# CPU.net
KiCad netlist of a schematic drawn in Altium Designer
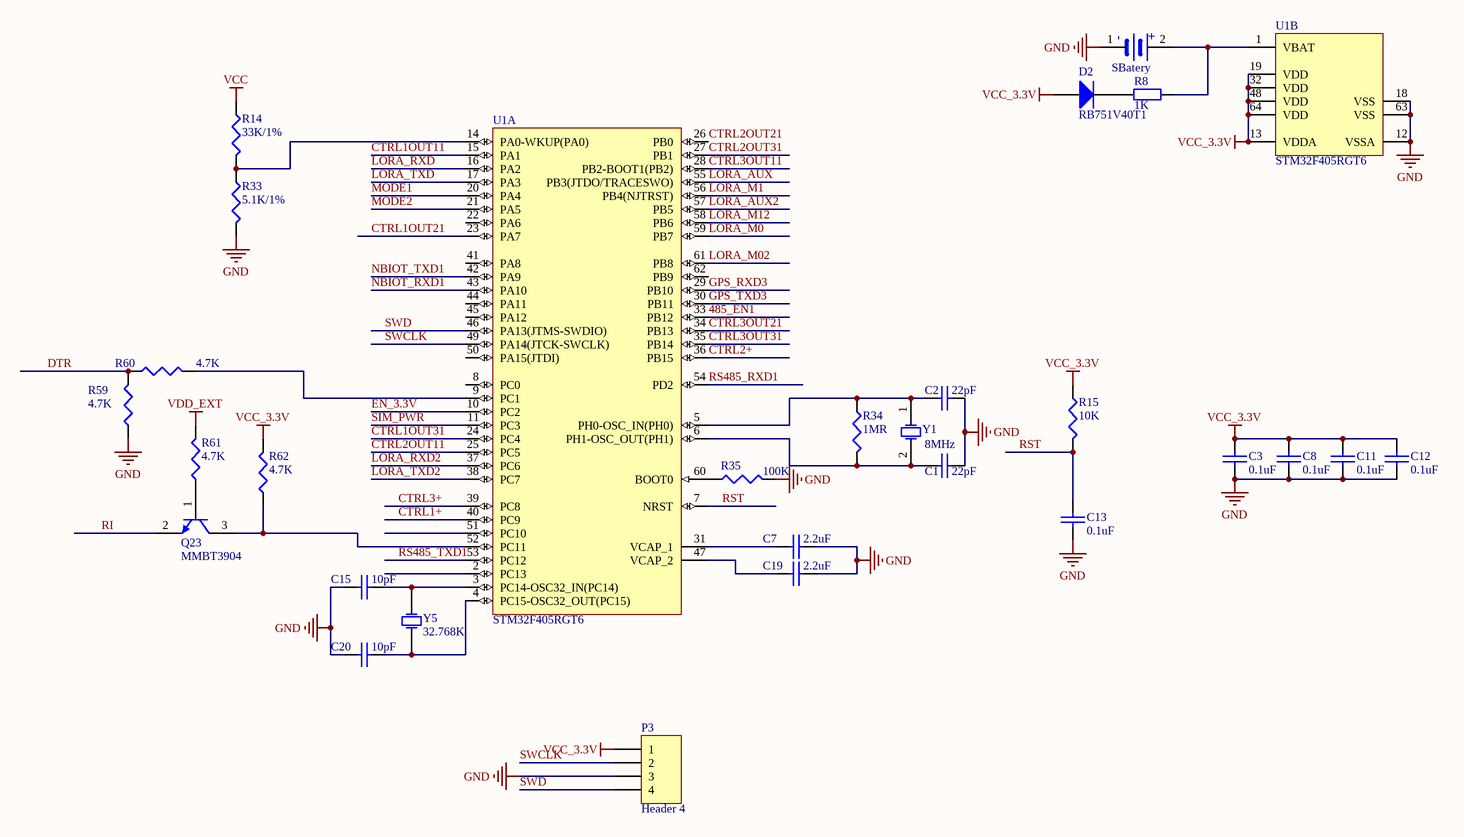
[diagram p0: CPU.SchDoc]

(export (version "E")
  (design (tool "Eeschema 10.0.6"))
  (components
    (comp (ref "C1")
      (value "22pF")
      (footprint "0603c")
      (description "Capacitor")
      (libsource (lib "SM") (part "CAP"))
    )
    (comp (ref "C2")
      (value "22pF")
      (footprint "0603c")
      (description "Capacitor")
      (libsource (lib "SM") (part "CAP"))
    )
    (comp (ref "C3")
      (value "0.1uF")
      (footprint "0603c")
      (description "Capacitor")
      (libsource (lib "SM") (part "CAP"))
    )
    (comp (ref "C7")
      (value "2.2uF")
      (footprint "0603c")
      (description "Capacitor")
      (libsource (lib "SM") (part "CAP"))
    )
    (comp (ref "C8")
      (value "0.1uF")
      (footprint "0603c")
      (description "Capacitor")
      (libsource (lib "SM") (part "CAP"))
    )
    (comp (ref "C11")
      (value "0.1uF")
      (footprint "0603c")
      (description "Capacitor")
      (libsource (lib "SM") (part "CAP"))
    )
    (comp (ref "C12")
      (value "0.1uF")
      (footprint "0603c")
      (description "Capacitor")
      (libsource (lib "SM") (part "CAP"))
    )
    (comp (ref "C13")
      (value "0.1uF")
      (footprint "0603c")
      (description "Capacitor")
      (libsource (lib "SM") (part "CAP"))
    )
    (comp (ref "C15")
      (value "10pF")
      (footprint "0603c")
      (description "Capacitor")
      (libsource (lib "SM") (part "CAP"))
    )
    (comp (ref "C19")
      (value "2.2uF")
      (footprint "0603c")
      (description "Capacitor")
      (libsource (lib "SM") (part "CAP"))
    )
    (comp (ref "C20")
      (value "10pF")
      (footprint "0603c")
      (description "Capacitor")
      (libsource (lib "SM") (part "CAP"))
    )
    (comp (ref "D2")
      (value "RB751V40T1")
      (footprint "SOD323")
      (description "Default Diode")
      (fields (field (name "PUBLISHER") "Altium Limited"))
      (libsource (lib "Miscellaneous Devices") (part "Diode"))
    )
    (comp (ref "P3")
      (value "Header 4")
      (footprint "HDR1X4")
      (description "Header, 4-Pin")
      (fields (field (name "PUBLISHER") "Altium Limited"))
      (libsource (lib "Miscellaneous Connectors") (part "Header 4"))
    )
    (comp (ref "Q23") (value "MMBT3904") (footprint "SOT23-3") (libsource (lib "Schlib1") (part "NPN")))
    (comp (ref "R8")
      (value "1K")
      (footprint "0603R")
      (description "Resistor")
      (fields (field (name "PUBLISHER") "Altium Limited"))
      (libsource (lib "Miscellaneous Devices") (part "Res2"))
    )
    (comp (ref "R14")
      (value "33K/1%")
      (footprint "0603R")
      (description "Resistor")
      (fields (field (name "PUBLISHER") "Altium Limited"))
      (libsource (lib "SM") (part "Res3"))
    )
    (comp (ref "R15")
      (value "10K")
      (footprint "0603R")
      (description "Resistor")
      (fields (field (name "PUBLISHER") "Altium Limited"))
      (libsource (lib "SM") (part "Res3"))
    )
    (comp (ref "R33")
      (value "5.1K/1%")
      (footprint "0603R")
      (description "Resistor")
      (fields (field (name "PUBLISHER") "Altium Limited"))
      (libsource (lib "SM") (part "Res3"))
    )
    (comp (ref "R34")
      (value "1MR")
      (footprint "0603R")
      (description "Resistor")
      (fields (field (name "PUBLISHER") "Altium Limited"))
      (libsource (lib "SM") (part "Res3"))
    )
    (comp (ref "R35")
      (value "100K")
      (footprint "0603R")
      (description "Resistor")
      (fields (field (name "PUBLISHER") "Altium Limited"))
      (libsource (lib "SM") (part "Res3"))
    )
    (comp (ref "R59")
      (value "4.7K")
      (footprint "0603R")
      (libsource (lib "ZWLIntegrated_Library") (part "RES1"))
    )
    (comp (ref "R60")
      (value "4.7K")
      (footprint "0603R")
      (libsource (lib "ZWLIntegrated_Library") (part "RES1"))
    )
    (comp (ref "R61")
      (value "4.7K")
      (footprint "0603R")
      (libsource (lib "ZWLIntegrated_Library") (part "RES1"))
    )
    (comp (ref "R62")
      (value "4.7K")
      (footprint "0603R")
      (libsource (lib "ZWLIntegrated_Library") (part "RES1"))
    )
    (comp (ref "SBatery")
      (value "SBatery")
      (footprint "MS621FE")
      (libsource (lib "Myself_1") (part "SBatery"))
    )
    (comp (ref "U1")
      (value "STM32F405RGT6")
      (footprint "LQFP-64")
      (fields (field (name "MANUFACTURER") "STMicroelectronics"))
      (libsource (lib "STMicroelectronics STM32 F4") (part "STM32F405RGT6"))
    )
    (comp (ref "Y1")
      (value "8MHz")
      (footprint "CRAY_5032")
      (description "Crystal Oscillator")
      (fields (field (name "PUBLISHER") "Altium Limited"))
      (libsource (lib "") (part "XTAL_1"))
    )
    (comp (ref "Y5")
      (value "32.768K")
      (footprint "32.768K")
      (description "Crystal Oscillator")
      (fields (field (name "PUBLISHER") "Altium Limited"))
      (libsource (lib "Miscellaneous Devices") (part "XTAL"))
    )
  )
  (nets
    (net (code "1") (name "/485_EN1") (class "Default")
      (node (ref "U1") (pin "33") (pinfunction "PB12_33") (pintype "bidirectional"))
    )
    (net (code "2") (name "/CTRL1+") (class "Default")
      (node (ref "U1") (pin "40") (pinfunction "PC9_40") (pintype "bidirectional"))
    )
    (net (code "3") (name "/CTRL1OUT11") (class "Default")
      (node (ref "U1") (pin "15") (pinfunction "PA1_15") (pintype "bidirectional"))
    )
    (net (code "4") (name "/CTRL1OUT21") (class "Default")
      (node (ref "U1") (pin "23") (pinfunction "PA7_23") (pintype "bidirectional"))
    )
    (net (code "5") (name "/CTRL1OUT31") (class "Default")
      (node (ref "U1") (pin "24") (pinfunction "PC4_24") (pintype "bidirectional"))
    )
    (net (code "6") (name "/CTRL2+") (class "Default")
      (node (ref "U1") (pin "36") (pinfunction "PB15_36") (pintype "bidirectional"))
    )
    (net (code "7") (name "/CTRL2OUT11") (class "Default")
      (node (ref "U1") (pin "25") (pinfunction "PC5_25") (pintype "bidirectional"))
    )
    (net (code "8") (name "/CTRL2OUT21") (class "Default")
      (node (ref "U1") (pin "26") (pinfunction "PB0_26") (pintype "bidirectional"))
    )
    (net (code "9") (name "/CTRL2OUT31") (class "Default")
      (node (ref "U1") (pin "27") (pinfunction "PB1_27") (pintype "bidirectional"))
    )
    (net (code "10") (name "/CTRL3+") (class "Default")
      (node (ref "U1") (pin "39") (pinfunction "PC8_39") (pintype "bidirectional"))
    )
    (net (code "11") (name "/CTRL3OUT11") (class "Default")
      (node (ref "U1") (pin "28") (pinfunction "PB2-BOOT1(PB2)_28") (pintype "bidirectional"))
    )
    (net (code "12") (name "/CTRL3OUT21") (class "Default")
      (node (ref "U1") (pin "34") (pinfunction "PB13_34") (pintype "bidirectional"))
    )
    (net (code "13") (name "/CTRL3OUT31") (class "Default")
      (node (ref "U1") (pin "35") (pinfunction "PB14_35") (pintype "bidirectional"))
    )
    (net (code "14") (name "/DTR") (class "Default")
      (node (ref "R59") (pin "2") (pinfunction "2_2") (pintype "passive"))
      (node (ref "R60") (pin "1") (pinfunction "1_1") (pintype "passive"))
    )
    (net (code "15") (name "/EN_3.3V") (class "Default")
      (node (ref "U1") (pin "10") (pinfunction "PC2_10") (pintype "bidirectional"))
    )
    (net (code "16") (name "/GPS_RXD3") (class "Default")
      (node (ref "U1") (pin "29") (pinfunction "PB10_29") (pintype "bidirectional"))
    )
    (net (code "17") (name "/GPS_TXD3") (class "Default")
      (node (ref "U1") (pin "30") (pinfunction "PB11_30") (pintype "bidirectional"))
    )
    (net (code "18") (name "/LORA_AUX") (class "Default")
      (node (ref "U1") (pin "55") (pinfunction "PB3(JTDO/TRACESWO)_55") (pintype "bidirectional"))
    )
    (net (code "19") (name "/LORA_AUX2") (class "Default")
      (node (ref "U1") (pin "57") (pinfunction "PB5_57") (pintype "bidirectional"))
    )
    (net (code "20") (name "/LORA_M0") (class "Default")
      (node (ref "U1") (pin "59") (pinfunction "PB7_59") (pintype "bidirectional"))
    )
    (net (code "21") (name "/LORA_M1") (class "Default")
      (node (ref "U1") (pin "56") (pinfunction "PB4(NJTRST)_56") (pintype "bidirectional"))
    )
    (net (code "22") (name "/LORA_M02") (class "Default")
      (node (ref "U1") (pin "61") (pinfunction "PB8_61") (pintype "bidirectional"))
    )
    (net (code "23") (name "/LORA_M12") (class "Default")
      (node (ref "U1") (pin "58") (pinfunction "PB6_58") (pintype "bidirectional"))
    )
    (net (code "24") (name "/LORA_RXD") (class "Default")
      (node (ref "U1") (pin "16") (pinfunction "PA2_16") (pintype "bidirectional"))
    )
    (net (code "25") (name "/LORA_RXD2") (class "Default")
      (node (ref "U1") (pin "37") (pinfunction "PC6_37") (pintype "bidirectional"))
    )
    (net (code "26") (name "/LORA_TXD") (class "Default")
      (node (ref "U1") (pin "17") (pinfunction "PA3_17") (pintype "bidirectional"))
    )
    (net (code "27") (name "/LORA_TXD2") (class "Default")
      (node (ref "U1") (pin "38") (pinfunction "PC7_38") (pintype "bidirectional"))
    )
    (net (code "28") (name "/MODE1") (class "Default")
      (node (ref "U1") (pin "20") (pinfunction "PA4_20") (pintype "bidirectional"))
    )
    (net (code "29") (name "/MODE2") (class "Default")
      (node (ref "U1") (pin "21") (pinfunction "PA5_21") (pintype "bidirectional"))
    )
    (net (code "30") (name "/NBIOT_RXD1") (class "Default")
      (node (ref "U1") (pin "43") (pinfunction "PA10_43") (pintype "bidirectional"))
    )
    (net (code "31") (name "/NBIOT_TXD1") (class "Default")
      (node (ref "U1") (pin "42") (pinfunction "PA9_42") (pintype "bidirectional"))
    )
    (net (code "32") (name "/RI") (class "Default")
      (node (ref "Q23") (pin "2") (pinfunction "E_2") (pintype "passive"))
    )
    (net (code "33") (name "/RS485_RXD1") (class "Default")
      (node (ref "U1") (pin "54") (pinfunction "PD2_54") (pintype "bidirectional"))
    )
    (net (code "34") (name "/RS485_TXD1") (class "Default")
      (node (ref "U1") (pin "53") (pinfunction "PC12_53") (pintype "bidirectional"))
    )
    (net (code "35") (name "/RST") (class "Default")
      (node (ref "C13") (pin "2") (pinfunction "2_2") (pintype "passive"))
      (node (ref "R15") (pin "2") (pinfunction "2_2") (pintype "passive"))
      (node (ref "U1") (pin "7") (pinfunction "NRST_7") (pintype "bidirectional"))
    )
    (net (code "36") (name "/SIM_PWR") (class "Default")
      (node (ref "U1") (pin "11") (pinfunction "PC3_11") (pintype "bidirectional"))
    )
    (net (code "37") (name "/SWCLK") (class "Default")
      (node (ref "P3") (pin "2") (pinfunction "2_2") (pintype "passive"))
      (node (ref "U1") (pin "49") (pinfunction "PA14(JTCK-SWCLK)_49") (pintype "bidirectional"))
    )
    (net (code "38") (name "/SWD") (class "Default")
      (node (ref "P3") (pin "4") (pinfunction "4_4") (pintype "passive"))
      (node (ref "U1") (pin "46") (pinfunction "PA13(JTMS-SWDIO)_46") (pintype "bidirectional"))
    )
    (net (code "39") (name "GND") (class "Default")
      (node (ref "C1") (pin "1") (pinfunction "1_1") (pintype "passive"))
      (node (ref "C11") (pin "1") (pinfunction "1_1") (pintype "passive"))
      (node (ref "C12") (pin "1") (pinfunction "1_1") (pintype "passive"))
      (node (ref "C13") (pin "1") (pinfunction "1_1") (pintype "passive"))
      (node (ref "C15") (pin "1") (pinfunction "1_1") (pintype "passive"))
      (node (ref "C19") (pin "1") (pinfunction "1_1") (pintype "passive"))
      (node (ref "C2") (pin "1") (pinfunction "1_1") (pintype "passive"))
      (node (ref "C20") (pin "1") (pinfunction "1_1") (pintype "passive"))
      (node (ref "C3") (pin "1") (pinfunction "1_1") (pintype "passive"))
      (node (ref "C7") (pin "1") (pinfunction "1_1") (pintype "passive"))
      (node (ref "C8") (pin "1") (pinfunction "1_1") (pintype "passive"))
      (node (ref "P3") (pin "3") (pinfunction "3_3") (pintype "passive"))
      (node (ref "R33") (pin "2") (pinfunction "2_2") (pintype "passive"))
      (node (ref "R35") (pin "2") (pinfunction "2_2") (pintype "passive"))
      (node (ref "R59") (pin "1") (pinfunction "1_1") (pintype "passive"))
      (node (ref "SBatery") (pin "1") (pinfunction "1_1") (pintype "passive"))
      (node (ref "U1") (pin "12") (pinfunction "VSSA_12") (pintype "power_in"))
      (node (ref "U1") (pin "18") (pinfunction "VSS_18") (pintype "power_in"))
      (node (ref "U1") (pin "63") (pinfunction "VSS_63") (pintype "power_in"))
    )
    (net (code "40") (name "Net-(D2-K)") (class "Default")
      (node (ref "D2") (pin "2") (pinfunction "K_2") (pintype "passive"))
      (node (ref "R8") (pin "1") (pinfunction "1_1") (pintype "passive"))
    )
    (net (code "41") (name "Net-(Q23-B)") (class "Default")
      (node (ref "Q23") (pin "1") (pinfunction "B_1") (pintype "passive"))
      (node (ref "R61") (pin "1") (pinfunction "1_1") (pintype "passive"))
    )
    (net (code "42") (name "Net-(Q23-C)") (class "Default")
      (node (ref "Q23") (pin "3") (pinfunction "C_3") (pintype "passive"))
      (node (ref "R62") (pin "1") (pinfunction "1_1") (pintype "passive"))
      (node (ref "U1") (pin "52") (pinfunction "PC11_52") (pintype "bidirectional"))
    )
    (net (code "43") (name "Net-(U1A-BOOT0)") (class "Default")
      (node (ref "R35") (pin "1") (pinfunction "1_1") (pintype "passive"))
      (node (ref "U1") (pin "60") (pinfunction "BOOT0_60") (pintype "input"))
    )
    (net (code "44") (name "Net-(U1A-PA0-WKUP(PA0))") (class "Default")
      (node (ref "R14") (pin "2") (pinfunction "2_2") (pintype "passive"))
      (node (ref "R33") (pin "1") (pinfunction "1_1") (pintype "passive"))
      (node (ref "U1") (pin "14") (pinfunction "PA0-WKUP(PA0)_14") (pintype "bidirectional"))
    )
    (net (code "45") (name "Net-(U1A-PC1)") (class "Default")
      (node (ref "R60") (pin "2") (pinfunction "2_2") (pintype "passive"))
      (node (ref "U1") (pin "9") (pinfunction "PC1_9") (pintype "bidirectional"))
    )
    (net (code "46") (name "Net-(U1A-PC14-OSC32_IN(PC14))") (class "Default")
      (node (ref "C15") (pin "2") (pinfunction "2_2") (pintype "passive"))
      (node (ref "U1") (pin "3") (pinfunction "PC14-OSC32_IN(PC14)_3") (pintype "bidirectional"))
      (node (ref "Y5") (pin "1") (pinfunction "OSC1_1") (pintype "passive"))
    )
    (net (code "47") (name "Net-(U1A-PC15-OSC32_OUT(PC15))") (class "Default")
      (node (ref "C20") (pin "2") (pinfunction "2_2") (pintype "passive"))
      (node (ref "U1") (pin "4") (pinfunction "PC15-OSC32_OUT(PC15)_4") (pintype "bidirectional"))
      (node (ref "Y5") (pin "2") (pinfunction "OSC2_2") (pintype "passive"))
    )
    (net (code "48") (name "Net-(U1A-PH0-OSC_IN(PH0))") (class "Default")
      (node (ref "C2") (pin "2") (pinfunction "2_2") (pintype "passive"))
      (node (ref "R34") (pin "1") (pinfunction "1_1") (pintype "passive"))
      (node (ref "U1") (pin "5") (pinfunction "PH0-OSC_IN(PH0)_5") (pintype "bidirectional"))
      (node (ref "Y1") (pin "1") (pinfunction "OSC1_1") (pintype "passive"))
    )
    (net (code "49") (name "Net-(U1A-PH1-OSC_OUT(PH1))") (class "Default")
      (node (ref "C1") (pin "2") (pinfunction "2_2") (pintype "passive"))
      (node (ref "R34") (pin "2") (pinfunction "2_2") (pintype "passive"))
      (node (ref "U1") (pin "6") (pinfunction "PH1-OSC_OUT(PH1)_6") (pintype "bidirectional"))
      (node (ref "Y1") (pin "2") (pinfunction "OSC2_2") (pintype "passive"))
    )
    (net (code "50") (name "Net-(U1A-VCAP_1)") (class "Default")
      (node (ref "C7") (pin "2") (pinfunction "2_2") (pintype "passive"))
      (node (ref "U1") (pin "31") (pinfunction "VCAP_1_31") (pintype "power_in"))
    )
    (net (code "51") (name "Net-(U1A-VCAP_2)") (class "Default")
      (node (ref "C19") (pin "2") (pinfunction "2_2") (pintype "passive"))
      (node (ref "U1") (pin "47") (pinfunction "VCAP_2_47") (pintype "power_in"))
    )
    (net (code "52") (name "Net-(U1B-VBAT)") (class "Default")
      (node (ref "R8") (pin "2") (pinfunction "2_2") (pintype "passive"))
      (node (ref "SBatery") (pin "2") (pinfunction "2_2") (pintype "passive"))
      (node (ref "U1") (pin "1") (pinfunction "VBAT_1") (pintype "power_in"))
    )
    (net (code "53") (name "VCC") (class "Default")
      (node (ref "R14") (pin "1") (pinfunction "1_1") (pintype "passive"))
    )
    (net (code "54") (name "VCC_3.3V") (class "Default")
      (node (ref "C11") (pin "2") (pinfunction "2_2") (pintype "passive"))
      (node (ref "C12") (pin "2") (pinfunction "2_2") (pintype "passive"))
      (node (ref "C3") (pin "2") (pinfunction "2_2") (pintype "passive"))
      (node (ref "C8") (pin "2") (pinfunction "2_2") (pintype "passive"))
      (node (ref "D2") (pin "1") (pinfunction "A_1") (pintype "passive"))
      (node (ref "P3") (pin "1") (pinfunction "1_1") (pintype "passive"))
      (node (ref "R15") (pin "1") (pinfunction "1_1") (pintype "passive"))
      (node (ref "R62") (pin "2") (pinfunction "2_2") (pintype "passive"))
      (node (ref "U1") (pin "13") (pinfunction "VDDA_13") (pintype "power_in"))
      (node (ref "U1") (pin "19") (pinfunction "VDD_19") (pintype "power_in"))
      (node (ref "U1") (pin "32") (pinfunction "VDD_32") (pintype "power_in"))
      (node (ref "U1") (pin "48") (pinfunction "VDD_48") (pintype "power_in"))
      (node (ref "U1") (pin "64") (pinfunction "VDD_64") (pintype "power_in"))
    )
    (net (code "55") (name "VDD_EXT") (class "Default")
      (node (ref "R61") (pin "2") (pinfunction "2_2") (pintype "passive"))
    )
    (net (code "56") (name "unconnected-(U1A-PA6-Pad22)") (class "Default")
      (node (ref "U1") (pin "22") (pinfunction "PA6_22") (pintype "bidirectional"))
    )
    (net (code "57") (name "unconnected-(U1A-PA8-Pad41)") (class "Default")
      (node (ref "U1") (pin "41") (pinfunction "PA8_41") (pintype "bidirectional"))
    )
    (net (code "58") (name "unconnected-(U1A-PA11-Pad44)") (class "Default")
      (node (ref "U1") (pin "44") (pinfunction "PA11_44") (pintype "bidirectional"))
    )
    (net (code "59") (name "unconnected-(U1A-PA12-Pad45)") (class "Default")
      (node (ref "U1") (pin "45") (pinfunction "PA12_45") (pintype "bidirectional"))
    )
    (net (code "60") (name "unconnected-(U1A-PA15(JTDI)-Pad50)") (class "Default")
      (node (ref "U1") (pin "50") (pinfunction "PA15(JTDI)_50") (pintype "bidirectional"))
    )
    (net (code "61") (name "unconnected-(U1A-PB9-Pad62)") (class "Default")
      (node (ref "U1") (pin "62") (pinfunction "PB9_62") (pintype "bidirectional"))
    )
    (net (code "62") (name "unconnected-(U1A-PC0-Pad8)") (class "Default")
      (node (ref "U1") (pin "8") (pinfunction "PC0_8") (pintype "bidirectional"))
    )
    (net (code "63") (name "unconnected-(U1A-PC10-Pad51)") (class "Default")
      (node (ref "U1") (pin "51") (pinfunction "PC10_51") (pintype "bidirectional"))
    )
    (net (code "64") (name "unconnected-(U1A-PC13-Pad2)") (class "Default")
      (node (ref "U1") (pin "2") (pinfunction "PC13_2") (pintype "bidirectional"))
    )
  )
)
